# Adafruit_1_14-inch_240x135_Color_TFT.net
KiCad netlist of a schematic drawn in EAGLE
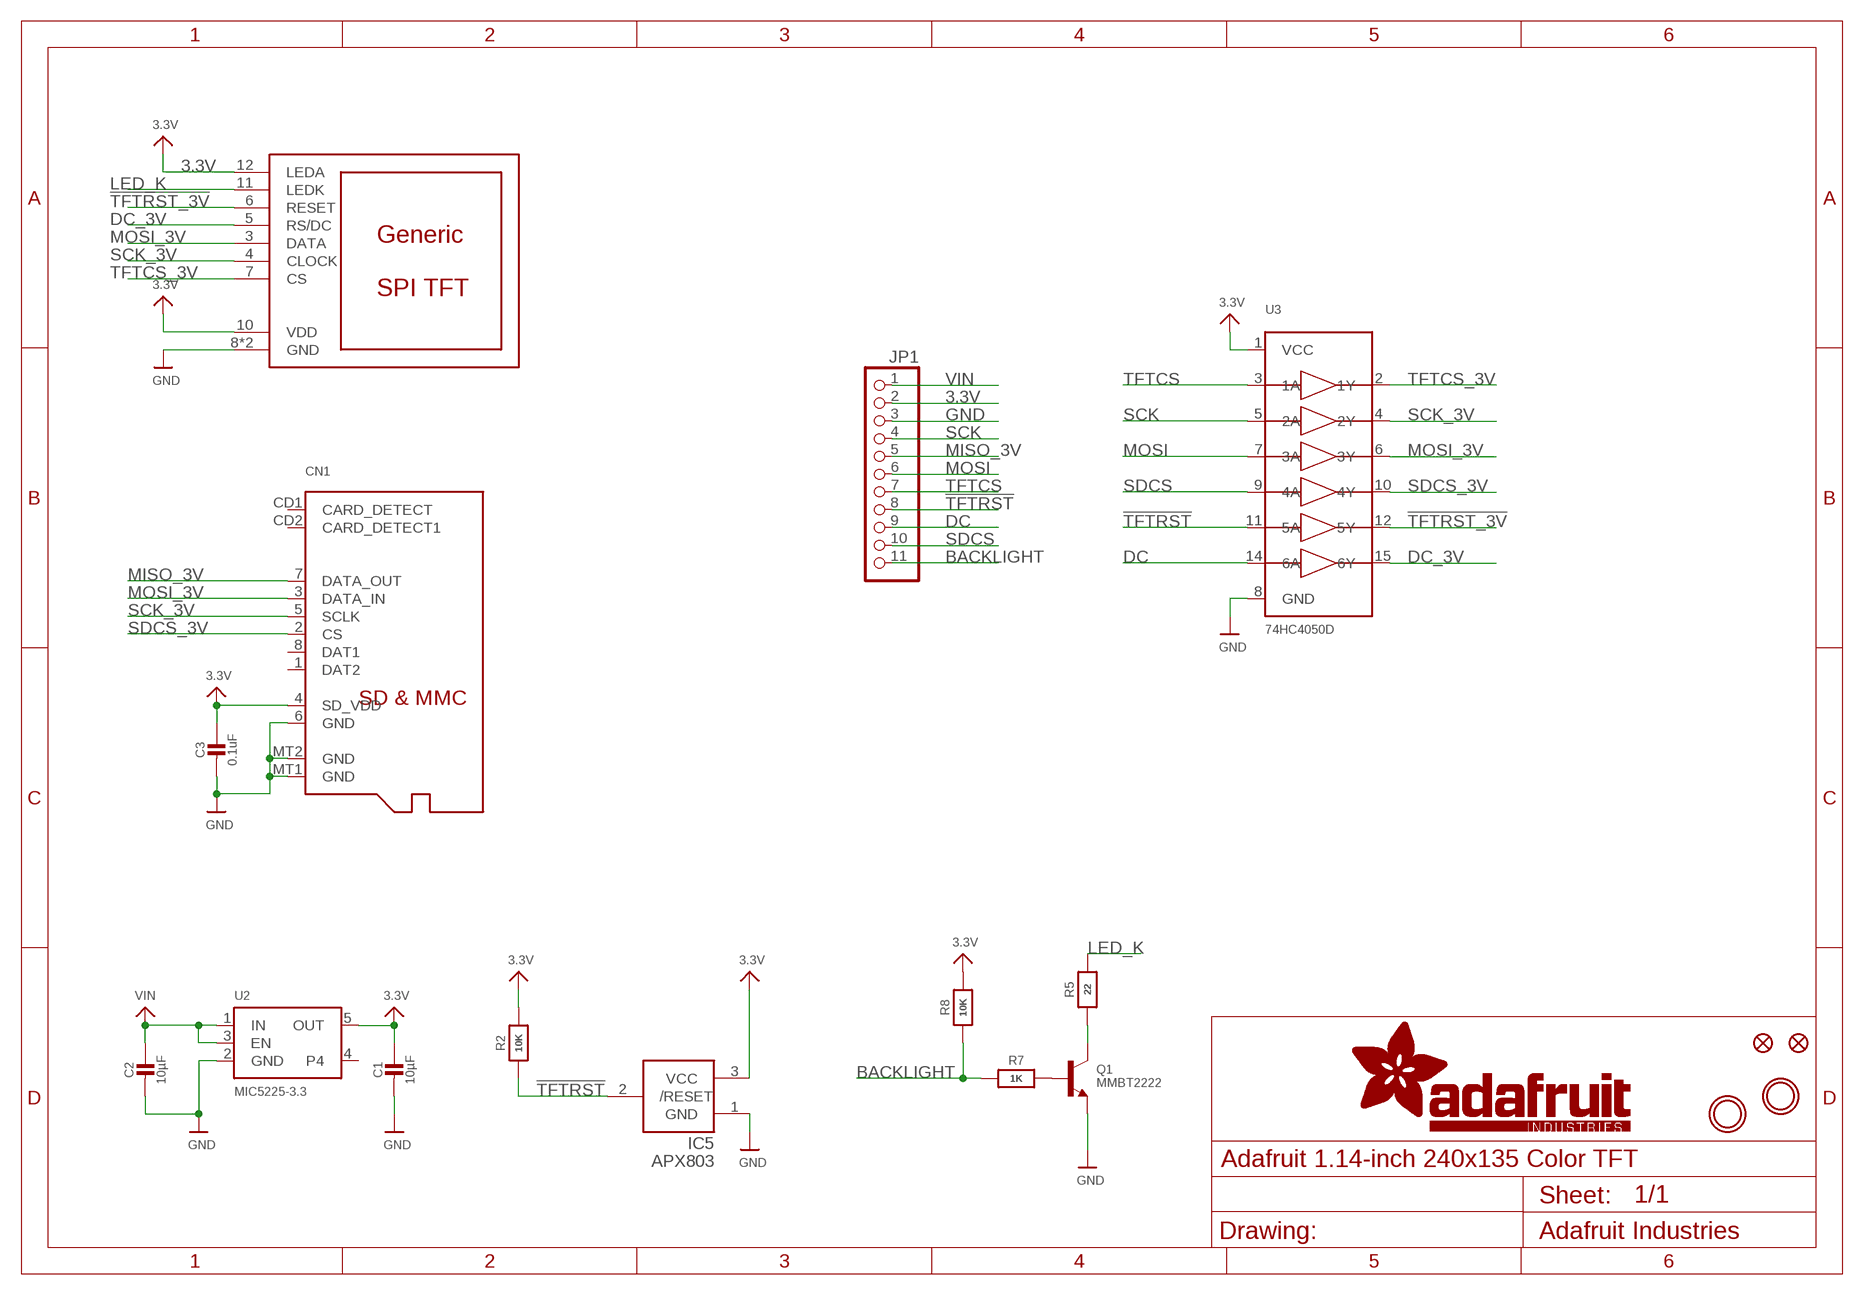
[diagram p0: schematic, sheet 1]

(export (version "E")
  (design (tool "Eeschema 10.0.6"))
  (components
    (comp (ref "C1")
      (value "10µF")
      (footprint "eagle-import:0805-NO")
      (libsource (lib "eagle-import") (part "CAP_CERAMIC0805-NOOUTLINE"))
    )
    (comp (ref "C2")
      (value "10µF")
      (footprint "eagle-import:0805-NO")
      (libsource (lib "eagle-import") (part "CAP_CERAMIC0805-NOOUTLINE"))
    )
    (comp (ref "C3")
      (value "0.1uF")
      (footprint "eagle-import:0805-NO")
      (libsource (lib "eagle-import") (part "CAP_CERAMIC0805-NOOUTLINE"))
    )
    (comp (ref "CN1")
      (value "MICROSD")
      (footprint "eagle-import:MICROSD")
      (libsource (lib "eagle-import") (part "MICROSD"))
    )
    (comp (ref "DISP1")
      (value "DISP_LCD_GENERIC_SPI_1.14IN_240X135_WRAPUNDER")
      (footprint "eagle-import:TFT_1.14IN_240X135_WRAPUNDER")
      (libsource (lib "eagle-import") (part "DISP_LCD_GENERIC_SPI_1.14IN_240X135_WRAPUNDER"))
    )
    (comp (ref "FID1")
      (value "FIDUCIAL_1MM")
      (footprint "eagle-import:FIDUCIAL_1MM")
      (libsource (lib "eagle-import") (part "FIDUCIAL_1MM"))
    )
    (comp (ref "FID2")
      (value "FIDUCIAL_1MM")
      (footprint "eagle-import:FIDUCIAL_1MM")
      (libsource (lib "eagle-import") (part "FIDUCIAL_1MM"))
    )
    (comp (ref "IC5")
      (value "APX803")
      (footprint "eagle-import:SOT23")
      (libsource (lib "eagle-import") (part "AXP083-SAG"))
    )
    (comp (ref "JP1")
      (value "HEADER-1X11")
      (footprint "eagle-import:1X11_ROUND")
      (libsource (lib "eagle-import") (part "HEADER-1X11"))
    )
    (comp (ref "Q1")
      (value "MMBT2222")
      (footprint "eagle-import:SOT23-WIDE")
      (libsource (lib "eagle-import") (part "TRANSISTOR_NPNWIDE"))
    )
    (comp (ref "R2")
      (value "10K")
      (footprint "eagle-import:0603-NO")
      (libsource (lib "eagle-import") (part "RESISTOR_0603_NOOUT"))
    )
    (comp (ref "R5")
      (value "22")
      (footprint "eagle-import:0603-NO")
      (libsource (lib "eagle-import") (part "RESISTOR_0603_NOOUT"))
    )
    (comp (ref "R7")
      (value "1K")
      (footprint "eagle-import:0603-NO")
      (libsource (lib "eagle-import") (part "RESISTOR_0603_NOOUT"))
    )
    (comp (ref "R8")
      (value "10K")
      (footprint "eagle-import:0603-NO")
      (libsource (lib "eagle-import") (part "RESISTOR_0603_NOOUT"))
    )
    (comp (ref "U$9")
      (value "MOUNTINGHOLE2.5")
      (footprint "eagle-import:MOUNTINGHOLE_2.5_PLATED")
      (libsource (lib "eagle-import") (part "MOUNTINGHOLE2.5"))
    )
    (comp (ref "U$10")
      (value "MOUNTINGHOLE2.5")
      (footprint "eagle-import:MOUNTINGHOLE_2.5_PLATED")
      (libsource (lib "eagle-import") (part "MOUNTINGHOLE2.5"))
    )
    (comp (ref "U2")
      (value "MIC5225-3.3")
      (footprint "eagle-import:SOT23-5")
      (libsource (lib "eagle-import") (part "VREG_SOT23-5"))
    )
    (comp (ref "U3")
      (value "74HC4050D")
      (footprint "eagle-import:SOIC16")
      (libsource (lib "eagle-import") (part "74HC4050D"))
    )
  )
  (nets
    (net (code "1") (name "/BACKLIGHT") (class "Default")
      (node (ref "JP1") (pin "11") (pinfunction "11_11") (pintype "passive"))
      (node (ref "R7") (pin "1") (pinfunction "1_1") (pintype "passive"))
      (node (ref "R8") (pin "1") (pinfunction "1_1") (pintype "passive"))
    )
    (net (code "2") (name "/DC") (class "Default")
      (node (ref "JP1") (pin "9") (pinfunction "9_9") (pintype "passive"))
      (node (ref "U3") (pin "14") (pinfunction "6A_14") (pintype "bidirectional"))
    )
    (net (code "3") (name "/DC_3V") (class "Default")
      (node (ref "DISP1") (pin "5") (pinfunction "RS/DC_5") (pintype "input"))
      (node (ref "U3") (pin "15") (pinfunction "6Y_15") (pintype "bidirectional"))
    )
    (net (code "4") (name "/LED_K") (class "Default")
      (node (ref "DISP1") (pin "11") (pinfunction "LEDK_11") (pintype "input"))
      (node (ref "R5") (pin "2") (pinfunction "2_2") (pintype "passive"))
    )
    (net (code "5") (name "/MISO_3V") (class "Default")
      (node (ref "CN1") (pin "7") (pinfunction "DATA_OUT_7") (pintype "output"))
      (node (ref "JP1") (pin "5") (pinfunction "5_5") (pintype "passive"))
    )
    (net (code "6") (name "/MOSI") (class "Default")
      (node (ref "JP1") (pin "6") (pinfunction "6_6") (pintype "passive"))
      (node (ref "U3") (pin "7") (pinfunction "3A_7") (pintype "bidirectional"))
    )
    (net (code "7") (name "/MOSI_3V") (class "Default")
      (node (ref "CN1") (pin "3") (pinfunction "DATA_IN_3") (pintype "input"))
      (node (ref "DISP1") (pin "3") (pinfunction "DATA_3") (pintype "bidirectional"))
      (node (ref "U3") (pin "6") (pinfunction "3Y_6") (pintype "bidirectional"))
    )
    (net (code "8") (name "/SCK") (class "Default")
      (node (ref "JP1") (pin "4") (pinfunction "4_4") (pintype "passive"))
      (node (ref "U3") (pin "5") (pinfunction "2A_5") (pintype "bidirectional"))
    )
    (net (code "9") (name "/SCK_3V") (class "Default")
      (node (ref "CN1") (pin "5") (pinfunction "SCLK_5") (pintype "input"))
      (node (ref "DISP1") (pin "4") (pinfunction "CLOCK_4") (pintype "input"))
      (node (ref "U3") (pin "4") (pinfunction "2Y_4") (pintype "bidirectional"))
    )
    (net (code "10") (name "/SDCS") (class "Default")
      (node (ref "JP1") (pin "10") (pinfunction "10_10") (pintype "passive"))
      (node (ref "U3") (pin "9") (pinfunction "4A_9") (pintype "bidirectional"))
    )
    (net (code "11") (name "/SDCS_3V") (class "Default")
      (node (ref "CN1") (pin "2") (pinfunction "CS_2") (pintype "input"))
      (node (ref "U3") (pin "10") (pinfunction "4Y_10") (pintype "bidirectional"))
    )
    (net (code "12") (name "/TFTCS") (class "Default")
      (node (ref "JP1") (pin "7") (pinfunction "7_7") (pintype "passive"))
      (node (ref "U3") (pin "3") (pinfunction "1A_3") (pintype "bidirectional"))
    )
    (net (code "13") (name "/TFTCS_3V") (class "Default")
      (node (ref "DISP1") (pin "7") (pinfunction "CS_7") (pintype "input"))
      (node (ref "U3") (pin "2") (pinfunction "1Y_2") (pintype "bidirectional"))
    )
    (net (code "14") (name "/~{TFTRST_3V}") (class "Default")
      (node (ref "DISP1") (pin "6") (pinfunction "RESET_6") (pintype "input"))
      (node (ref "U3") (pin "12") (pinfunction "5Y_12") (pintype "bidirectional"))
    )
    (net (code "15") (name "/~{TFTRST}") (class "Default")
      (node (ref "IC5") (pin "2") (pinfunction "/RESET_2") (pintype "output"))
      (node (ref "JP1") (pin "8") (pinfunction "8_8") (pintype "passive"))
      (node (ref "R2") (pin "1") (pinfunction "1_1") (pintype "passive"))
      (node (ref "U3") (pin "11") (pinfunction "5A_11") (pintype "bidirectional"))
    )
    (net (code "16") (name "3.3V") (class "Default")
      (node (ref "C1") (pin "1") (pinfunction "1_1") (pintype "passive"))
      (node (ref "C3") (pin "1") (pinfunction "1_1") (pintype "passive"))
      (node (ref "CN1") (pin "4") (pinfunction "SD_VDD_4") (pintype "power_in"))
      (node (ref "DISP1") (pin "10") (pinfunction "VDD_10") (pintype "power_in"))
      (node (ref "DISP1") (pin "12") (pinfunction "LEDA_12") (pintype "input"))
      (node (ref "IC5") (pin "3") (pinfunction "VCC_3") (pintype "power_in"))
      (node (ref "JP1") (pin "2") (pinfunction "2_2") (pintype "passive"))
      (node (ref "R2") (pin "2") (pinfunction "2_2") (pintype "passive"))
      (node (ref "R8") (pin "2") (pinfunction "2_2") (pintype "passive"))
      (node (ref "U2") (pin "5") (pinfunction "OUT_5") (pintype "power_in"))
      (node (ref "U3") (pin "1") (pinfunction "VCC_1") (pintype "bidirectional"))
    )
    (net (code "17") (name "GND") (class "Default")
      (node (ref "C1") (pin "2") (pinfunction "2_2") (pintype "passive"))
      (node (ref "C2") (pin "2") (pinfunction "2_2") (pintype "passive"))
      (node (ref "C3") (pin "2") (pinfunction "2_2") (pintype "passive"))
      (node (ref "CN1") (pin "6") (pinfunction "GND_6") (pintype "power_in"))
      (node (ref "CN1") (pin "MT1") (pinfunction "GND_MT1") (pintype "power_in"))
      (node (ref "CN1") (pin "MT2") (pinfunction "GND_MT2") (pintype "power_in"))
      (node (ref "DISP1") (pin "13") (pinfunction "GND_13") (pintype "power_in"))
      (node (ref "DISP1") (pin "8") (pinfunction "GND_8") (pintype "power_in"))
      (node (ref "IC5") (pin "1") (pinfunction "GND_1") (pintype "power_in"))
      (node (ref "JP1") (pin "3") (pinfunction "3_3") (pintype "passive"))
      (node (ref "Q1") (pin "2") (pinfunction "E_2") (pintype "passive"))
      (node (ref "U2") (pin "2") (pinfunction "GND_2") (pintype "power_in"))
      (node (ref "U3") (pin "8") (pinfunction "GND_8") (pintype "bidirectional"))
    )
    (net (code "18") (name "Net-(Q1-B)") (class "Default")
      (node (ref "Q1") (pin "1") (pinfunction "B_1") (pintype "passive"))
      (node (ref "R7") (pin "2") (pinfunction "2_2") (pintype "passive"))
    )
    (net (code "19") (name "Net-(Q1-C)") (class "Default")
      (node (ref "Q1") (pin "3") (pinfunction "C_3") (pintype "passive"))
      (node (ref "R5") (pin "1") (pinfunction "1_1") (pintype "passive"))
    )
    (net (code "20") (name "VIN") (class "Default")
      (node (ref "C2") (pin "1") (pinfunction "1_1") (pintype "passive"))
      (node (ref "JP1") (pin "1") (pinfunction "1_1") (pintype "passive"))
      (node (ref "U2") (pin "1") (pinfunction "IN_1") (pintype "power_in"))
      (node (ref "U2") (pin "3") (pinfunction "EN_3") (pintype "input"))
    )
    (net (code "21") (name "unconnected-(CN1-CARD_DETECT-PadCD1)") (class "Default")
      (node (ref "CN1") (pin "CD1") (pinfunction "CARD_DETECT_CD1") (pintype "passive"))
    )
    (net (code "22") (name "unconnected-(CN1-CARD_DETECT1-PadCD2)") (class "Default")
      (node (ref "CN1") (pin "CD2") (pinfunction "CARD_DETECT1_CD2") (pintype "passive"))
    )
    (net (code "23") (name "unconnected-(CN1-DAT1-Pad8)") (class "Default")
      (node (ref "CN1") (pin "8") (pinfunction "DAT1_8") (pintype "bidirectional"))
    )
    (net (code "24") (name "unconnected-(CN1-DAT2-Pad1)") (class "Default")
      (node (ref "CN1") (pin "1") (pinfunction "DAT2_1") (pintype "bidirectional"))
    )
    (net (code "25") (name "unconnected-(U2-P4-Pad4)") (class "Default")
      (node (ref "U2") (pin "4") (pinfunction "P4_4") (pintype "bidirectional"))
    )
  )
)
